# 5V_Supply_Alt_1.net
KiCad netlist of a schematic drawn in Altium Designer
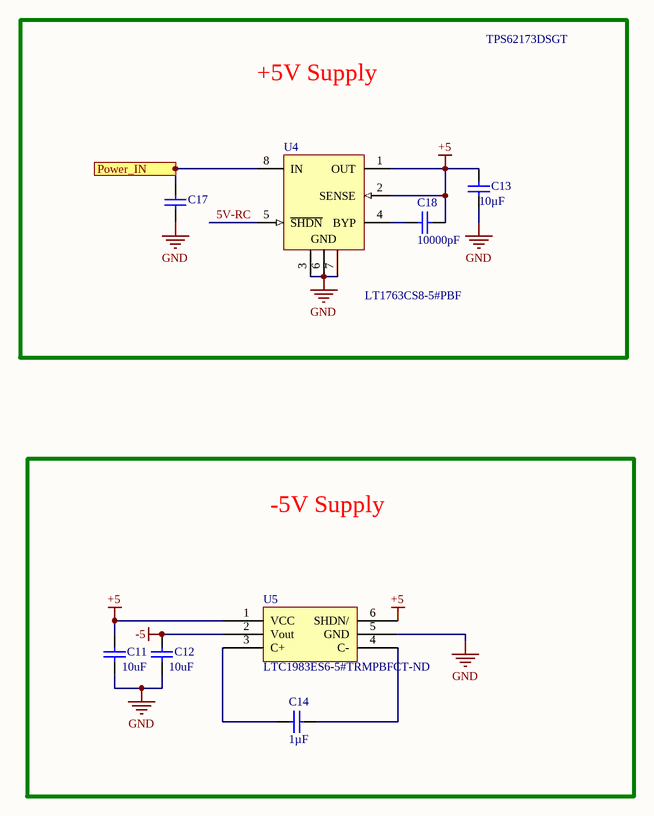
[diagram p0: 5V_Supply_Alt_1.SchDoc]

(export (version "E")
  (design (tool "Eeschema 10.0.6"))
  (components
    (comp (ref "C11")
      (value "CAP CER 10UF 6.3V X5R 1206")
      (footprint "CAPC1206(3216)130_N")
      (fields
        (field (name "MANUFACTURER") "Taiyo Yuden")
        (field (name "MANUFACTURER PART NUMBER") "JMK316BJ106ML-T")
        (field (name "TOLERANCE") "±20%")
        (field (name "CAPACITANCE") "10uF")
      )
      (libsource (lib "Altium Content Vault") (part "CMP-1037-04913-1"))
    )
    (comp (ref "C12")
      (value "CAP CER 10UF 6.3V X5R 1206")
      (footprint "CAPC1206(3216)130_N")
      (fields
        (field (name "MANUFACTURER") "Taiyo Yuden")
        (field (name "MANUFACTURER PART NUMBER") "JMK316BJ106ML-T")
        (field (name "TOLERANCE") "±20%")
        (field (name "CAPACITANCE") "10uF")
      )
      (libsource (lib "Altium Content Vault") (part "CMP-1037-04913-1"))
    )
    (comp (ref "C13")
      (value "CAP CER 1UF 50V X7R 1210")
      (footprint "CAPC1206(3216)130_N")
      (fields
        (field (name "MANUFACTURER") "Murata Electronics North America")
        (field (name "MANUFACTURER PART NUMBER") "GRM32RR71H105KA01L")
        (field (name "CAPACITANCE") "10µF")
        (field (name "TOLERANCE") "±10%")
      )
      (libsource (lib "Altium Content Vault") (part "CMP-1037-04913-1"))
    )
    (comp (ref "C14")
      (value "CAP CER 1UF 10V X5R 0805")
      (footprint "CAPC1206(3216)130_N")
      (fields
        (field (name "CAPACITANCE") "1µF")
        (field (name "MANUFACTURER") "Taiyo Yuden")
        (field (name "MANUFACTURER PART NUMBER") "LMK212BJ105MD-T")
        (field (name "TOLERANCE") "±20%")
      )
      (libsource (lib "Altium Content Vault") (part "CMP-1037-04913-1"))
    )
    (comp (ref "C17")
      (value "1uF")
      (footprint "CAPC1206(3216)130_N")
      (libsource (lib "Altium Content Vault") (part "CMP-1037-04913-1"))
    )
    (comp (ref "C18")
      (value "CAP CER 1UF 50V X7R 1210")
      (footprint "CAPC1206(3216)130_N")
      (fields
        (field (name "MANUFACTURER") "Murata Electronics North America")
        (field (name "MANUFACTURER PART NUMBER") "GRM32RR71H105KA01L")
        (field (name "CAPACITANCE") "10000pF")
        (field (name "TOLERANCE") "±10%")
      )
      (libsource (lib "Altium Content Vault") (part "CMP-1037-04913-1"))
    )
    (comp (ref "U4")
      (value "LT1763CS8-5#PBF")
      (footprint "LT-S8-8_M")
      (fields (field (name "MANUFACTURER") "Linear Technology"))
      (libsource (lib "Altium Content Vault") (part "LT-LT1763-S8-8"))
    )
    (comp (ref "U5")
      (value "LTC1983ES6-5#TRMPBF")
      (footprint "SOT95P323X100-6N")
      (fields
        (field (name "SUPPLIER PART NUMBER 1") "LTC1983ES6-5#TRMPBFCT-ND")
        (field (name "MANUFACTURER") "Linear Technology/Analog Devices")
        (field (name "BASE PART NUMBER") "LTC1983-5")
      )
      (libsource (lib "ZLS_Schematic_lib") (part "LTC1983ES6-5#TRMPBF"))
    )
  )
  (nets
    (net (code "1") (name "+5") (class "Default")
      (node (ref "C11") (pin "2") (pinfunction "2_2") (pintype "passive"))
      (node (ref "C13") (pin "2") (pinfunction "2_2") (pintype "passive"))
      (node (ref "C18") (pin "1") (pinfunction "1_1") (pintype "passive"))
      (node (ref "U4") (pin "1") (pinfunction "OUT_1") (pintype "power_in"))
      (node (ref "U4") (pin "2") (pinfunction "SENSE_2") (pintype "input"))
      (node (ref "U5") (pin "1") (pinfunction "VCC_1") (pintype "passive"))
      (node (ref "U5") (pin "6") (pinfunction "SHDN/_6") (pintype "passive"))
    )
    (net (code "2") (name "-5") (class "Default")
      (node (ref "C12") (pin "2") (pinfunction "2_2") (pintype "passive"))
      (node (ref "U5") (pin "2") (pinfunction "Vout_2") (pintype "passive"))
    )
    (net (code "3") (name "/5V-RC") (class "Default")
      (node (ref "U4") (pin "5") (pinfunction "~{SHDN}_5") (pintype "input"))
    )
    (net (code "4") (name "/Power_IN") (class "Default")
      (node (ref "C17") (pin "2") (pinfunction "2_2") (pintype "passive"))
      (node (ref "U4") (pin "8") (pinfunction "IN_8") (pintype "power_in"))
    )
    (net (code "5") (name "GND") (class "Default")
      (node (ref "C11") (pin "1") (pinfunction "1_1") (pintype "passive"))
      (node (ref "C12") (pin "1") (pinfunction "1_1") (pintype "passive"))
      (node (ref "C13") (pin "1") (pinfunction "1_1") (pintype "passive"))
      (node (ref "C17") (pin "1") (pinfunction "1_1") (pintype "passive"))
      (node (ref "U4") (pin "3") (pinfunction "GND_3") (pintype "power_in"))
      (node (ref "U4") (pin "6") (pinfunction "GND_6") (pintype "power_in"))
      (node (ref "U4") (pin "7") (pinfunction "GND_7") (pintype "power_in"))
      (node (ref "U5") (pin "5") (pinfunction "GND_5") (pintype "passive"))
    )
    (net (code "6") (name "Net-(U4-BYP)") (class "Default")
      (node (ref "C18") (pin "2") (pinfunction "2_2") (pintype "passive"))
      (node (ref "U4") (pin "4") (pinfunction "BYP_4") (pintype "passive"))
    )
    (net (code "7") (name "Net-(U5-C+)") (class "Default")
      (node (ref "C14") (pin "2") (pinfunction "2_2") (pintype "passive"))
      (node (ref "U5") (pin "3") (pinfunction "C+_3") (pintype "passive"))
    )
    (net (code "8") (name "Net-(U5-C-)") (class "Default")
      (node (ref "C14") (pin "1") (pinfunction "1_1") (pintype "passive"))
      (node (ref "U5") (pin "4") (pinfunction "C-_4") (pintype "passive"))
    )
  )
)
